# R1_Power.net
KiCad netlist of a schematic drawn in EAGLE
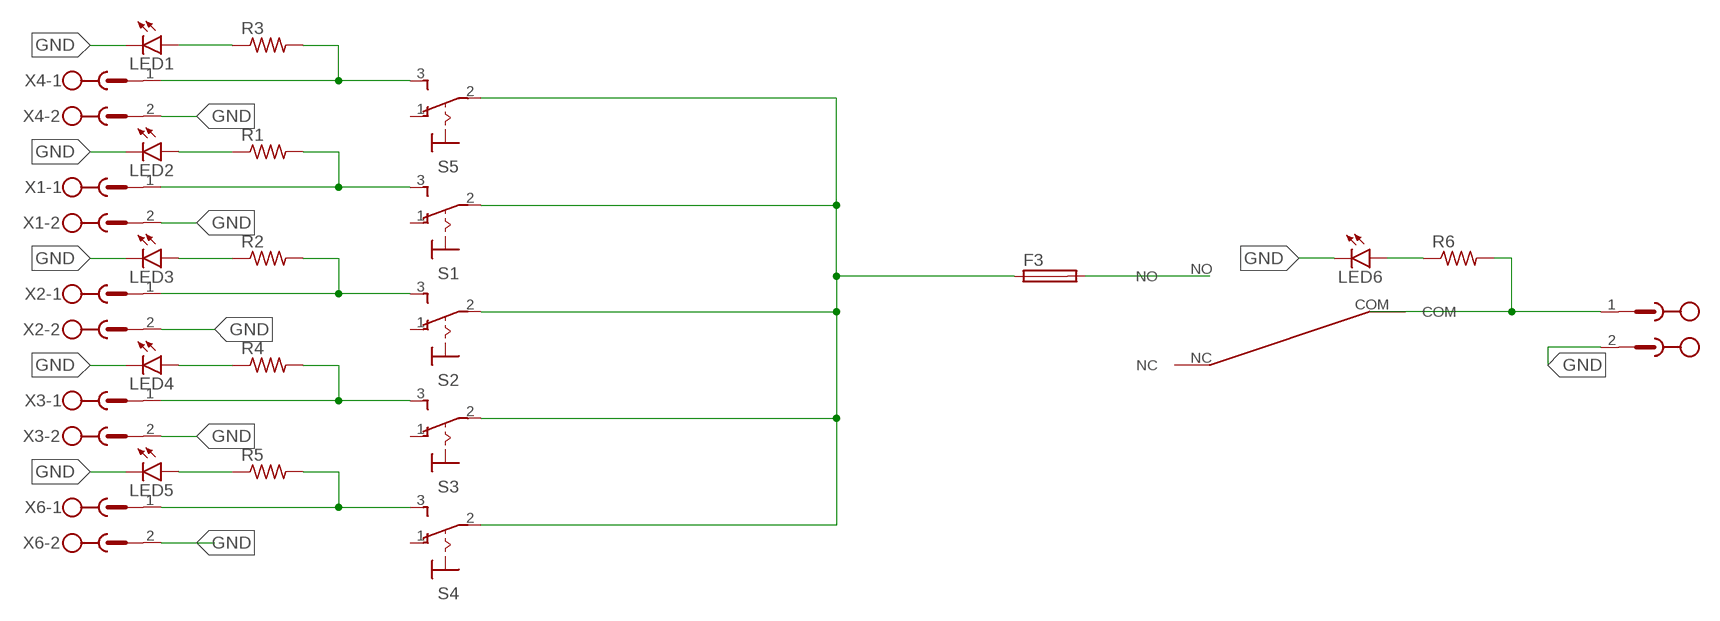
[diagram p0: schematic, sheet 1]

(export (version "E")
  (design (tool "Eeschema 10.0.6"))
  (components
    (comp (ref "F3")
      (value "SH22,5")
      (footprint "eagle-import:SH22,5")
      (fields (field (name "MF") "SCHURTER") (field (name "MPN") "0031.8201"))
      (libsource (lib "eagle-import") (part "SH22,5"))
    )
    (comp (ref "LED1")
      (value "LED3MM")
      (footprint "eagle-import:LED3MM")
      (libsource (lib "eagle-import") (part "LED3MM"))
    )
    (comp (ref "LED2")
      (value "LED3MM")
      (footprint "eagle-import:LED3MM")
      (libsource (lib "eagle-import") (part "LED3MM"))
    )
    (comp (ref "LED3")
      (value "LED3MM")
      (footprint "eagle-import:LED3MM")
      (libsource (lib "eagle-import") (part "LED3MM"))
    )
    (comp (ref "LED4")
      (value "LED3MM")
      (footprint "eagle-import:LED3MM")
      (libsource (lib "eagle-import") (part "LED3MM"))
    )
    (comp (ref "LED5")
      (value "LED3MM")
      (footprint "eagle-import:LED3MM")
      (libsource (lib "eagle-import") (part "LED3MM"))
    )
    (comp (ref "LED6")
      (value "LED3MM")
      (footprint "eagle-import:LED3MM")
      (libsource (lib "eagle-import") (part "LED3MM"))
    )
    (comp (ref "MAINSWITCH")
      (value "SPDT_TOGGLE_1SPDT_TOGGLE_2")
      (footprint "eagle-import:SPDT_TOGGLE_1")
      (libsource (lib "eagle-import") (part "SPDT_TOGGLE_1SPDT_TOGGLE_2"))
    )
    (comp (ref "R1")
      (value "R-US_0207/10")
      (footprint "eagle-import:0207_10")
      (libsource (lib "eagle-import") (part "R-US_0207/10"))
    )
    (comp (ref "R2")
      (value "R-US_0207/10")
      (footprint "eagle-import:0207_10")
      (libsource (lib "eagle-import") (part "R-US_0207/10"))
    )
    (comp (ref "R3")
      (value "R-US_0207/10")
      (footprint "eagle-import:0207_10")
      (libsource (lib "eagle-import") (part "R-US_0207/10"))
    )
    (comp (ref "R4")
      (value "R-US_0207/10")
      (footprint "eagle-import:0207_10")
      (libsource (lib "eagle-import") (part "R-US_0207/10"))
    )
    (comp (ref "R5")
      (value "R-US_0207/10")
      (footprint "eagle-import:0207_10")
      (libsource (lib "eagle-import") (part "R-US_0207/10"))
    )
    (comp (ref "R6")
      (value "R-US_0207/10")
      (footprint "eagle-import:0207_10")
      (libsource (lib "eagle-import") (part "R-US_0207/10"))
    )
    (comp (ref "S1")
      (value "320-916")
      (footprint "eagle-import:320-916")
      (libsource (lib "eagle-import") (part "320-916"))
    )
    (comp (ref "S2")
      (value "320-916")
      (footprint "eagle-import:320-916")
      (libsource (lib "eagle-import") (part "320-916"))
    )
    (comp (ref "S3")
      (value "320-916")
      (footprint "eagle-import:320-916")
      (libsource (lib "eagle-import") (part "320-916"))
    )
    (comp (ref "S4")
      (value "320-916")
      (footprint "eagle-import:320-916")
      (libsource (lib "eagle-import") (part "320-916"))
    )
    (comp (ref "S5")
      (value "320-916")
      (footprint "eagle-import:320-916")
      (libsource (lib "eagle-import") (part "320-916"))
    )
    (comp (ref "VCC")
      (value "MSTBV2")
      (footprint "eagle-import:MSTBV2")
      (libsource (lib "eagle-import") (part "MSTBV2"))
    )
    (comp (ref "X1")
      (value "MSTBV2")
      (footprint "eagle-import:MSTBV2")
      (libsource (lib "eagle-import") (part "MSTBV2"))
    )
    (comp (ref "X2")
      (value "MSTBV2")
      (footprint "eagle-import:MSTBV2")
      (libsource (lib "eagle-import") (part "MSTBV2"))
    )
    (comp (ref "X3")
      (value "MSTBV2")
      (footprint "eagle-import:MSTBV2")
      (libsource (lib "eagle-import") (part "MSTBV2"))
    )
    (comp (ref "X4")
      (value "MSTBV2")
      (footprint "eagle-import:MSTBV2")
      (libsource (lib "eagle-import") (part "MSTBV2"))
    )
    (comp (ref "X6")
      (value "MSTBV2")
      (footprint "eagle-import:MSTBV2")
      (libsource (lib "eagle-import") (part "MSTBV2"))
    )
  )
  (nets
    (net (code "1") (name "GND") (class "Default")
      (node (ref "LED1") (pin "K") (pinfunction "C_K") (pintype "passive"))
      (node (ref "LED2") (pin "K") (pinfunction "C_K") (pintype "passive"))
      (node (ref "LED3") (pin "K") (pinfunction "C_K") (pintype "passive"))
      (node (ref "LED4") (pin "K") (pinfunction "C_K") (pintype "passive"))
      (node (ref "LED5") (pin "K") (pinfunction "C_K") (pintype "passive"))
      (node (ref "LED6") (pin "K") (pinfunction "C_K") (pintype "passive"))
      (node (ref "VCC") (pin "2") (pinfunction "SK_2") (pintype "passive"))
      (node (ref "X1") (pin "2") (pinfunction "SK_2") (pintype "passive"))
      (node (ref "X2") (pin "2") (pinfunction "SK_2") (pintype "passive"))
      (node (ref "X3") (pin "2") (pinfunction "SK_2") (pintype "passive"))
      (node (ref "X4") (pin "2") (pinfunction "SK_2") (pintype "passive"))
      (node (ref "X6") (pin "2") (pinfunction "SK_2") (pintype "passive"))
    )
    (net (code "2") (name "Net-(F3-Pad2)") (class "Default")
      (node (ref "F3") (pin "2") (pinfunction "2_2") (pintype "passive"))
      (node (ref "MAINSWITCH") (pin "NO") (pinfunction "NO_NO") (pintype "bidirectional"))
    )
    (net (code "3") (name "Net-(LED1-PadA)") (class "Default")
      (node (ref "LED1") (pin "A") (pinfunction "A_A") (pintype "passive"))
      (node (ref "R3") (pin "1") (pinfunction "1_1") (pintype "passive"))
    )
    (net (code "4") (name "Net-(LED2-PadA)") (class "Default")
      (node (ref "LED2") (pin "A") (pinfunction "A_A") (pintype "passive"))
      (node (ref "R1") (pin "1") (pinfunction "1_1") (pintype "passive"))
    )
    (net (code "5") (name "Net-(LED3-PadA)") (class "Default")
      (node (ref "LED3") (pin "A") (pinfunction "A_A") (pintype "passive"))
      (node (ref "R2") (pin "1") (pinfunction "1_1") (pintype "passive"))
    )
    (net (code "6") (name "Net-(LED4-PadA)") (class "Default")
      (node (ref "LED4") (pin "A") (pinfunction "A_A") (pintype "passive"))
      (node (ref "R4") (pin "1") (pinfunction "1_1") (pintype "passive"))
    )
    (net (code "7") (name "Net-(LED5-PadA)") (class "Default")
      (node (ref "LED5") (pin "A") (pinfunction "A_A") (pintype "passive"))
      (node (ref "R5") (pin "1") (pinfunction "1_1") (pintype "passive"))
    )
    (net (code "8") (name "Net-(LED6-PadA)") (class "Default")
      (node (ref "LED6") (pin "A") (pinfunction "A_A") (pintype "passive"))
      (node (ref "R6") (pin "1") (pinfunction "1_1") (pintype "passive"))
    )
    (net (code "9") (name "Net-(S1-P)") (class "Default")
      (node (ref "F3") (pin "1") (pinfunction "1_1") (pintype "passive"))
      (node (ref "S1") (pin "2") (pinfunction "P_2") (pintype "passive"))
      (node (ref "S2") (pin "2") (pinfunction "P_2") (pintype "passive"))
      (node (ref "S3") (pin "2") (pinfunction "P_2") (pintype "passive"))
      (node (ref "S4") (pin "2") (pinfunction "P_2") (pintype "passive"))
      (node (ref "S5") (pin "2") (pinfunction "P_2") (pintype "passive"))
    )
    (net (code "10") (name "Net-(S1-S)") (class "Default")
      (node (ref "R1") (pin "2") (pinfunction "2_2") (pintype "passive"))
      (node (ref "S1") (pin "3") (pinfunction "S_3") (pintype "passive"))
      (node (ref "X1") (pin "1") (pinfunction "SK_1") (pintype "passive"))
    )
    (net (code "11") (name "Net-(S2-S)") (class "Default")
      (node (ref "R2") (pin "2") (pinfunction "2_2") (pintype "passive"))
      (node (ref "S2") (pin "3") (pinfunction "S_3") (pintype "passive"))
      (node (ref "X2") (pin "1") (pinfunction "SK_1") (pintype "passive"))
    )
    (net (code "12") (name "Net-(S3-S)") (class "Default")
      (node (ref "R4") (pin "2") (pinfunction "2_2") (pintype "passive"))
      (node (ref "S3") (pin "3") (pinfunction "S_3") (pintype "passive"))
      (node (ref "X3") (pin "1") (pinfunction "SK_1") (pintype "passive"))
    )
    (net (code "13") (name "Net-(S4-S)") (class "Default")
      (node (ref "R5") (pin "2") (pinfunction "2_2") (pintype "passive"))
      (node (ref "S4") (pin "3") (pinfunction "S_3") (pintype "passive"))
      (node (ref "X6") (pin "1") (pinfunction "SK_1") (pintype "passive"))
    )
    (net (code "14") (name "Net-(S5-S)") (class "Default")
      (node (ref "R3") (pin "2") (pinfunction "2_2") (pintype "passive"))
      (node (ref "S5") (pin "3") (pinfunction "S_3") (pintype "passive"))
      (node (ref "X4") (pin "1") (pinfunction "SK_1") (pintype "passive"))
    )
    (net (code "15") (name "Net-(VCCA-SK)") (class "Default")
      (node (ref "MAINSWITCH") (pin "COM") (pinfunction "COM_COM") (pintype "bidirectional"))
      (node (ref "R6") (pin "2") (pinfunction "2_2") (pintype "passive"))
      (node (ref "VCC") (pin "1") (pinfunction "SK_1") (pintype "passive"))
    )
    (net (code "16") (name "unconnected-(MAINSWITCH-PadNC)") (class "Default")
      (node (ref "MAINSWITCH") (pin "NC") (pinfunction "NC_NC") (pintype "bidirectional"))
    )
    (net (code "17") (name "unconnected-(S1-O-Pad1)") (class "Default")
      (node (ref "S1") (pin "1") (pinfunction "O_1") (pintype "passive"))
    )
    (net (code "18") (name "unconnected-(S2-O-Pad1)") (class "Default")
      (node (ref "S2") (pin "1") (pinfunction "O_1") (pintype "passive"))
    )
    (net (code "19") (name "unconnected-(S3-O-Pad1)") (class "Default")
      (node (ref "S3") (pin "1") (pinfunction "O_1") (pintype "passive"))
    )
    (net (code "20") (name "unconnected-(S4-O-Pad1)") (class "Default")
      (node (ref "S4") (pin "1") (pinfunction "O_1") (pintype "passive"))
    )
    (net (code "21") (name "unconnected-(S5-O-Pad1)") (class "Default")
      (node (ref "S5") (pin "1") (pinfunction "O_1") (pintype "passive"))
    )
  )
)
